# MotorControl.net
KiCad netlist of a schematic drawn in Altium Designer
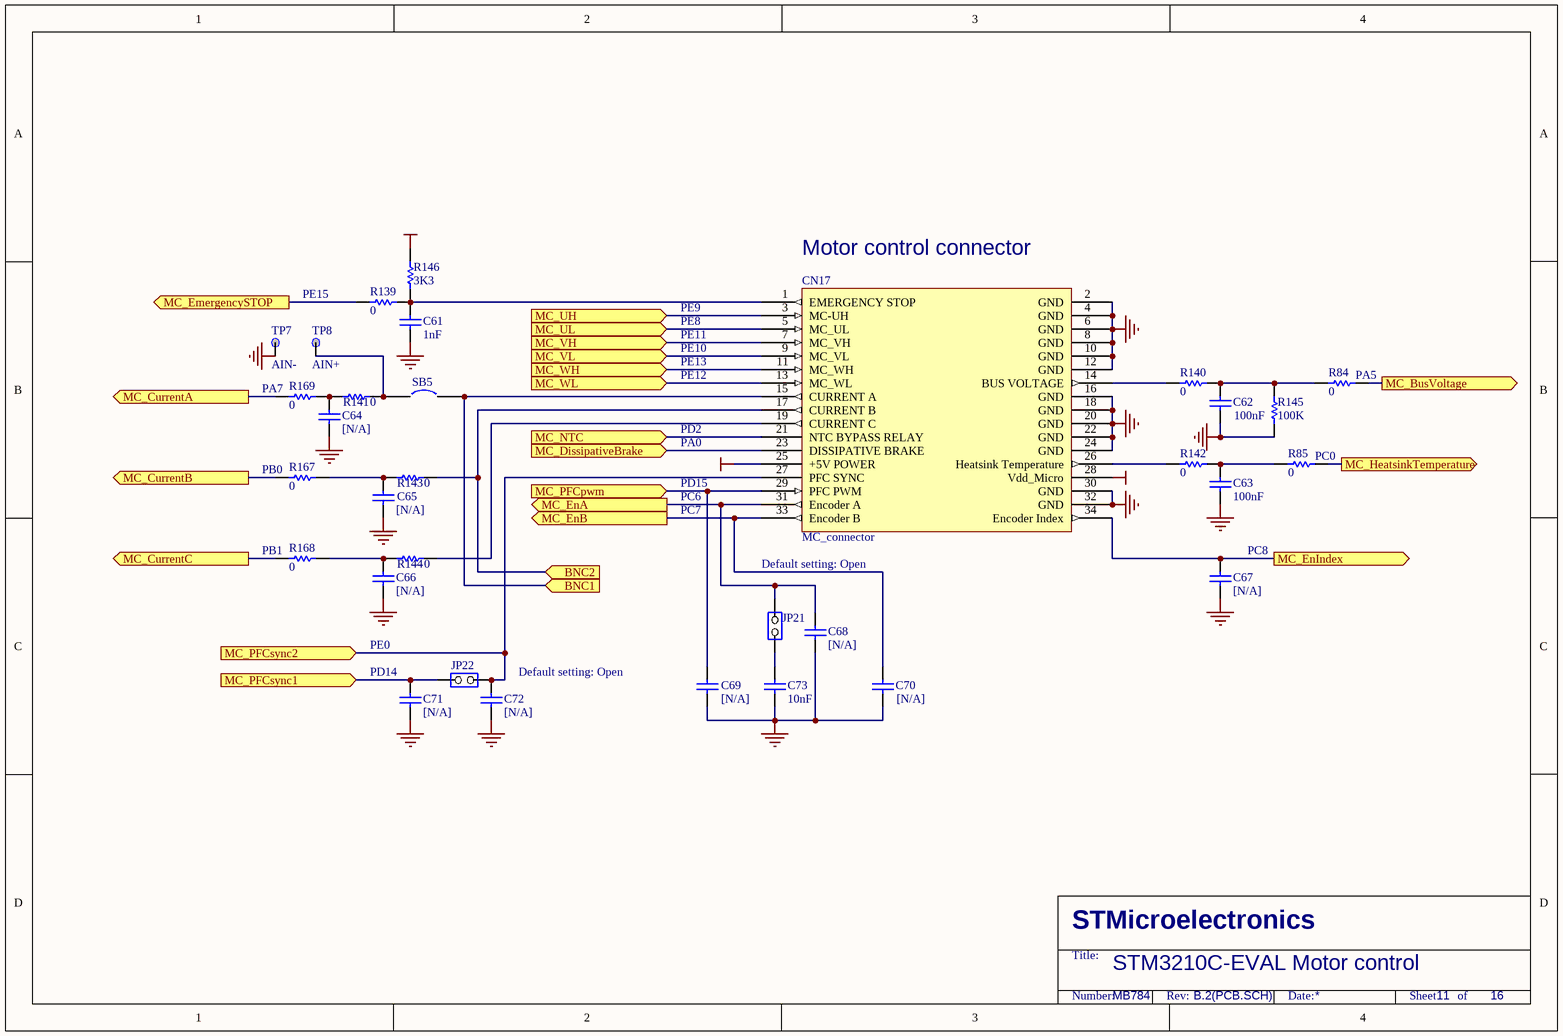
[diagram p0: MotorControl.SchDoc]

(export (version "E")
  (design (tool "Eeschema 10.0.6"))
  (components
    (comp (ref "C61")
      (value "1nF")
      (footprint "0603C")
      (description "Capacitor")
      (fields (field (name "PUBLISHER") "Altium Limited"))
      (libsource (lib "Miscellaneous Devices") (part "CAP"))
    )
    (comp (ref "C62")
      (value "100nF")
      (footprint "0603C")
      (description "Capacitor")
      (fields (field (name "PUBLISHER") "Altium Limited"))
      (libsource (lib "Miscellaneous Devices") (part "cap"))
    )
    (comp (ref "C63")
      (value "100nF")
      (footprint "0603C")
      (description "Capacitor")
      (fields (field (name "PUBLISHER") "Altium Limited"))
      (libsource (lib "Miscellaneous Devices") (part "cap"))
    )
    (comp (ref "C64")
      (value "[N/A]")
      (footprint "0603C")
      (description "Capacitor")
      (fields (field (name "PUBLISHER") "Altium Limited"))
      (libsource (lib "Miscellaneous Devices") (part "cap"))
    )
    (comp (ref "C65")
      (value "[N/A]")
      (footprint "0603C")
      (description "Capacitor")
      (fields (field (name "PUBLISHER") "Altium Limited"))
      (libsource (lib "Miscellaneous Devices") (part "cap"))
    )
    (comp (ref "C66")
      (value "[N/A]")
      (footprint "0603C")
      (description "Capacitor")
      (fields (field (name "PUBLISHER") "Altium Limited"))
      (libsource (lib "Miscellaneous Devices") (part "cap"))
    )
    (comp (ref "C67")
      (value "[N/A]")
      (footprint "0603C")
      (description "Capacitor")
      (fields (field (name "PUBLISHER") "Altium Limited"))
      (libsource (lib "Miscellaneous Devices") (part "cap"))
    )
    (comp (ref "C68")
      (value "[N/A]")
      (footprint "0603C")
      (description "Capacitor")
      (fields (field (name "PUBLISHER") "Altium Limited"))
      (libsource (lib "Miscellaneous Devices") (part "cap"))
    )
    (comp (ref "C69")
      (value "[N/A]")
      (footprint "0603C")
      (description "Capacitor")
      (fields (field (name "PUBLISHER") "Altium Limited"))
      (libsource (lib "Miscellaneous Devices") (part "cap"))
    )
    (comp (ref "C70")
      (value "[N/A]")
      (footprint "0603C")
      (description "Capacitor")
      (fields (field (name "PUBLISHER") "Altium Limited"))
      (libsource (lib "Miscellaneous Devices") (part "cap"))
    )
    (comp (ref "C71")
      (value "[N/A]")
      (footprint "0603C")
      (description "Capacitor")
      (fields (field (name "PUBLISHER") "Altium Limited"))
      (libsource (lib "Miscellaneous Devices") (part "cap"))
    )
    (comp (ref "C72")
      (value "[N/A]")
      (footprint "0603C")
      (description "Capacitor")
      (fields (field (name "PUBLISHER") "Altium Limited"))
      (libsource (lib "Miscellaneous Devices") (part "cap"))
    )
    (comp (ref "C73")
      (value "10nF")
      (footprint "0603C")
      (description "Capacitor")
      (fields (field (name "PUBLISHER") "Altium Limited"))
      (libsource (lib "Miscellaneous Devices") (part "cap"))
    )
    (comp (ref "CN17")
      (value "MC_connector")
      (footprint "IDC34S")
      (libsource (lib "MB525") (part "MC_connector"))
    )
    (comp (ref "JP21") (value "~") (footprint "SIP2") (libsource (lib "*") (part "JP2")))
    (comp (ref "JP22") (value "~") (footprint "SIP2") (libsource (lib "*") (part "JP2")))
    (comp (ref "R84")
      (value "0")
      (footprint "0603R")
      (description "Resistor")
      (fields (field (name "PUBLISHER") "Altium Limited"))
      (libsource (lib "Miscellaneous Devices") (part "Res1"))
    )
    (comp (ref "R85")
      (value "0")
      (footprint "0603R")
      (description "Resistor")
      (fields (field (name "PUBLISHER") "Altium Limited"))
      (libsource (lib "Miscellaneous Devices") (part "Res1"))
    )
    (comp (ref "R139")
      (value "0")
      (footprint "0603R")
      (description "Resistor")
      (fields (field (name "PUBLISHER") "Altium Limited"))
      (libsource (lib "Miscellaneous Devices") (part "Res1"))
    )
    (comp (ref "R140")
      (value "0")
      (footprint "0603R")
      (description "Resistor")
      (fields (field (name "PUBLISHER") "Altium Limited"))
      (libsource (lib "Miscellaneous Devices") (part "Res1"))
    )
    (comp (ref "R141")
      (value "0")
      (footprint "0603R")
      (description "Resistor")
      (fields (field (name "PUBLISHER") "Altium Limited"))
      (libsource (lib "Miscellaneous Devices") (part "Res1"))
    )
    (comp (ref "R142")
      (value "0")
      (footprint "0603R")
      (description "Resistor")
      (fields (field (name "PUBLISHER") "Altium Limited"))
      (libsource (lib "Miscellaneous Devices") (part "Res1"))
    )
    (comp (ref "R143")
      (value "0")
      (footprint "0603R")
      (description "Resistor")
      (fields (field (name "PUBLISHER") "Altium Limited"))
      (libsource (lib "Miscellaneous Devices") (part "Res1"))
    )
    (comp (ref "R144")
      (value "0")
      (footprint "0603R")
      (description "Resistor")
      (fields (field (name "PUBLISHER") "Altium Limited"))
      (libsource (lib "Miscellaneous Devices") (part "Res1"))
    )
    (comp (ref "R145")
      (value "100K")
      (footprint "0603R")
      (description "Resistor")
      (fields (field (name "PUBLISHER") "Altium Limited"))
      (libsource (lib "Miscellaneous Devices") (part "Res1"))
    )
    (comp (ref "R146")
      (value "3K3")
      (footprint "0603R")
      (description "Resistor")
      (fields (field (name "PUBLISHER") "Altium Limited"))
      (libsource (lib "Miscellaneous Devices") (part "Res1"))
    )
    (comp (ref "R167")
      (value "0")
      (footprint "0603R")
      (description "Resistor")
      (fields (field (name "PUBLISHER") "Altium Limited"))
      (libsource (lib "Miscellaneous Devices") (part "Res1"))
    )
    (comp (ref "R168")
      (value "0")
      (footprint "0603R")
      (description "Resistor")
      (fields (field (name "PUBLISHER") "Altium Limited"))
      (libsource (lib "Miscellaneous Devices") (part "Res1"))
    )
    (comp (ref "R169")
      (value "0")
      (footprint "0603R")
      (description "Resistor")
      (fields (field (name "PUBLISHER") "Altium Limited"))
      (libsource (lib "Miscellaneous Devices") (part "Res1"))
    )
    (comp (ref "SB5")
      (value "~")
      (footprint "JP2_SMD")
      (description "Circuit Breaker")
      (fields (field (name "PUBLISHER") "Altium Limited"))
      (libsource (lib "Miscellaneous Devices") (part "Circuit Breaker"))
    )
    (comp (ref "TP7") (value "AIN-") (footprint "TP") (libsource (lib "*") (part "TP")))
    (comp (ref "TP8") (value "AIN+") (footprint "TP") (libsource (lib "*") (part "TP")))
  )
  (nets
    (net (code "1") (name "+3V3") (class "Default")
      (node (ref "CN17") (pin "28") (pinfunction "Vdd_Micro_28") (pintype "power_in"))
      (node (ref "R146") (pin "2") (pinfunction "2_2") (pintype "passive"))
    )
    (net (code "2") (name "+5V") (class "Default")
      (node (ref "CN17") (pin "25") (pinfunction "+5V_POWER_25") (pintype "power_in"))
    )
    (net (code "3") (name "/BNC1") (class "Default")
      (node (ref "CN17") (pin "15") (pinfunction "CURRENT_A_15") (pintype "output"))
      (node (ref "SB5") (pin "2") (pinfunction "2_2") (pintype "passive"))
    )
    (net (code "4") (name "/BNC2") (class "Default")
      (node (ref "CN17") (pin "17") (pinfunction "CURRENT_B_17") (pintype "output"))
      (node (ref "R143") (pin "2") (pinfunction "2_2") (pintype "passive"))
    )
    (net (code "5") (name "/MC_BusVoltage") (class "Default")
      (node (ref "R84") (pin "2") (pinfunction "2_2") (pintype "passive"))
    )
    (net (code "6") (name "/MC_CurrentA") (class "Default")
      (node (ref "R169") (pin "1") (pinfunction "1_1") (pintype "passive"))
    )
    (net (code "7") (name "/MC_CurrentB") (class "Default")
      (node (ref "R167") (pin "1") (pinfunction "1_1") (pintype "passive"))
    )
    (net (code "8") (name "/MC_CurrentC") (class "Default")
      (node (ref "R168") (pin "1") (pinfunction "1_1") (pintype "passive"))
    )
    (net (code "9") (name "/MC_DissipativeBrake") (class "Default")
      (node (ref "CN17") (pin "23") (pinfunction "DISSIPATIVE_BRAKE_23") (pintype "passive"))
    )
    (net (code "10") (name "/MC_EmergencySTOP") (class "Default")
      (node (ref "R139") (pin "2") (pinfunction "2_2") (pintype "passive"))
    )
    (net (code "11") (name "/MC_EnA") (class "Default")
      (node (ref "C68") (pin "2") (pinfunction "2_2") (pintype "passive"))
      (node (ref "CN17") (pin "31") (pinfunction "Encoder_A_31") (pintype "output"))
      (node (ref "JP21") (pin "1") (pinfunction "COMMON_1") (pintype "passive"))
    )
    (net (code "12") (name "/MC_EnB") (class "Default")
      (node (ref "C70") (pin "2") (pinfunction "2_2") (pintype "passive"))
      (node (ref "CN17") (pin "33") (pinfunction "Encoder_B_33") (pintype "output"))
    )
    (net (code "13") (name "/MC_EnIndex") (class "Default")
      (node (ref "C67") (pin "2") (pinfunction "2_2") (pintype "passive"))
      (node (ref "CN17") (pin "34") (pinfunction "Encoder_Index_34") (pintype "output"))
    )
    (net (code "14") (name "/MC_HeatsinkTemperature") (class "Default")
      (node (ref "R85") (pin "2") (pinfunction "2_2") (pintype "passive"))
    )
    (net (code "15") (name "/MC_NTC") (class "Default")
      (node (ref "CN17") (pin "21") (pinfunction "NTC_BYPASS_RELAY_21") (pintype "passive"))
    )
    (net (code "16") (name "/MC_PFCpwm") (class "Default")
      (node (ref "C69") (pin "2") (pinfunction "2_2") (pintype "passive"))
      (node (ref "CN17") (pin "29") (pinfunction "PFC_PWM_29") (pintype "input"))
    )
    (net (code "17") (name "/MC_PFCsync1") (class "Default")
      (node (ref "C71") (pin "2") (pinfunction "2_2") (pintype "passive"))
      (node (ref "JP22") (pin "2") (pinfunction "NO_2") (pintype "passive"))
    )
    (net (code "18") (name "/MC_PFCsync2") (class "Default")
      (node (ref "C72") (pin "2") (pinfunction "2_2") (pintype "passive"))
      (node (ref "CN17") (pin "27") (pinfunction "PFC_SYNC_27") (pintype "passive"))
      (node (ref "JP22") (pin "1") (pinfunction "COMMON_1") (pintype "passive"))
    )
    (net (code "19") (name "/MC_UH") (class "Default")
      (node (ref "CN17") (pin "3") (pinfunction "MC-UH_3") (pintype "input"))
    )
    (net (code "20") (name "/MC_UL") (class "Default")
      (node (ref "CN17") (pin "5") (pinfunction "MC_UL_5") (pintype "input"))
    )
    (net (code "21") (name "/MC_VH") (class "Default")
      (node (ref "CN17") (pin "7") (pinfunction "MC_VH_7") (pintype "input"))
    )
    (net (code "22") (name "/MC_VL") (class "Default")
      (node (ref "CN17") (pin "9") (pinfunction "MC_VL_9") (pintype "input"))
    )
    (net (code "23") (name "/MC_WH") (class "Default")
      (node (ref "CN17") (pin "11") (pinfunction "MC_WH_11") (pintype "input"))
    )
    (net (code "24") (name "/MC_WL") (class "Default")
      (node (ref "CN17") (pin "13") (pinfunction "MC_WL_13") (pintype "input"))
    )
    (net (code "25") (name "GND") (class "Default")
      (node (ref "C61") (pin "1") (pinfunction "1_1") (pintype "passive"))
      (node (ref "C62") (pin "1") (pinfunction "1_1") (pintype "passive"))
      (node (ref "C63") (pin "1") (pinfunction "1_1") (pintype "passive"))
      (node (ref "C64") (pin "1") (pinfunction "1_1") (pintype "passive"))
      (node (ref "C65") (pin "1") (pinfunction "1_1") (pintype "passive"))
      (node (ref "C66") (pin "1") (pinfunction "1_1") (pintype "passive"))
      (node (ref "C67") (pin "1") (pinfunction "1_1") (pintype "passive"))
      (node (ref "C68") (pin "1") (pinfunction "1_1") (pintype "passive"))
      (node (ref "C69") (pin "1") (pinfunction "1_1") (pintype "passive"))
      (node (ref "C70") (pin "1") (pinfunction "1_1") (pintype "passive"))
      (node (ref "C71") (pin "1") (pinfunction "1_1") (pintype "passive"))
      (node (ref "C72") (pin "1") (pinfunction "1_1") (pintype "passive"))
      (node (ref "C73") (pin "1") (pinfunction "1_1") (pintype "passive"))
      (node (ref "CN17") (pin "10") (pinfunction "GND_10") (pintype "power_in"))
      (node (ref "CN17") (pin "12") (pinfunction "GND_12") (pintype "power_in"))
      (node (ref "CN17") (pin "16") (pinfunction "GND_16") (pintype "power_in"))
      (node (ref "CN17") (pin "18") (pinfunction "GND_18") (pintype "power_in"))
      (node (ref "CN17") (pin "2") (pinfunction "GND_2") (pintype "power_in"))
      (node (ref "CN17") (pin "20") (pinfunction "GND_20") (pintype "power_in"))
      (node (ref "CN17") (pin "22") (pinfunction "GND_22") (pintype "power_in"))
      (node (ref "CN17") (pin "24") (pinfunction "GND_24") (pintype "power_in"))
      (node (ref "CN17") (pin "30") (pinfunction "GND_30") (pintype "power_in"))
      (node (ref "CN17") (pin "32") (pinfunction "GND_32") (pintype "power_in"))
      (node (ref "CN17") (pin "4") (pinfunction "GND_4") (pintype "power_in"))
      (node (ref "CN17") (pin "6") (pinfunction "GND_6") (pintype "power_in"))
      (node (ref "CN17") (pin "8") (pinfunction "GND_8") (pintype "power_in"))
      (node (ref "R145") (pin "1") (pinfunction "1_1") (pintype "passive"))
      (node (ref "TP7") (pin "1") (pinfunction "1_1") (pintype "passive"))
    )
    (net (code "26") (name "Net-(C62-Pad2)") (class "Default")
      (node (ref "C62") (pin "2") (pinfunction "2_2") (pintype "passive"))
      (node (ref "R140") (pin "2") (pinfunction "2_2") (pintype "passive"))
      (node (ref "R145") (pin "2") (pinfunction "2_2") (pintype "passive"))
      (node (ref "R84") (pin "1") (pinfunction "1_1") (pintype "passive"))
    )
    (net (code "27") (name "Net-(C63-Pad2)") (class "Default")
      (node (ref "C63") (pin "2") (pinfunction "2_2") (pintype "passive"))
      (node (ref "R142") (pin "2") (pinfunction "2_2") (pintype "passive"))
      (node (ref "R85") (pin "1") (pinfunction "1_1") (pintype "passive"))
    )
    (net (code "28") (name "Net-(C64-Pad2)") (class "Default")
      (node (ref "C64") (pin "2") (pinfunction "2_2") (pintype "passive"))
      (node (ref "R141") (pin "1") (pinfunction "1_1") (pintype "passive"))
      (node (ref "R169") (pin "2") (pinfunction "2_2") (pintype "passive"))
    )
    (net (code "29") (name "Net-(C65-Pad2)") (class "Default")
      (node (ref "C65") (pin "2") (pinfunction "2_2") (pintype "passive"))
      (node (ref "R143") (pin "1") (pinfunction "1_1") (pintype "passive"))
      (node (ref "R167") (pin "2") (pinfunction "2_2") (pintype "passive"))
    )
    (net (code "30") (name "Net-(C66-Pad2)") (class "Default")
      (node (ref "C66") (pin "2") (pinfunction "2_2") (pintype "passive"))
      (node (ref "R144") (pin "1") (pinfunction "1_1") (pintype "passive"))
      (node (ref "R168") (pin "2") (pinfunction "2_2") (pintype "passive"))
    )
    (net (code "31") (name "Net-(CN17-BUS_VOLTAGE)") (class "Default")
      (node (ref "CN17") (pin "14") (pinfunction "BUS_VOLTAGE_14") (pintype "output"))
      (node (ref "R140") (pin "1") (pinfunction "1_1") (pintype "passive"))
    )
    (net (code "32") (name "Net-(CN17-CURRENT_C)") (class "Default")
      (node (ref "CN17") (pin "19") (pinfunction "CURRENT_C_19") (pintype "output"))
      (node (ref "R144") (pin "2") (pinfunction "2_2") (pintype "passive"))
    )
    (net (code "33") (name "Net-(CN17-EMERGENCY_STOP)") (class "Default")
      (node (ref "C61") (pin "2") (pinfunction "2_2") (pintype "passive"))
      (node (ref "CN17") (pin "1") (pinfunction "EMERGENCY_STOP_1") (pintype "output"))
      (node (ref "R139") (pin "1") (pinfunction "1_1") (pintype "passive"))
      (node (ref "R146") (pin "1") (pinfunction "1_1") (pintype "passive"))
    )
    (net (code "34") (name "Net-(CN17-Heatsink_Temperature)") (class "Default")
      (node (ref "CN17") (pin "26") (pinfunction "Heatsink_Temperature_26") (pintype "output"))
      (node (ref "R142") (pin "1") (pinfunction "1_1") (pintype "passive"))
    )
    (net (code "35") (name "Net-(JP21-NO)") (class "Default")
      (node (ref "C73") (pin "2") (pinfunction "2_2") (pintype "passive"))
      (node (ref "JP21") (pin "2") (pinfunction "NO_2") (pintype "passive"))
    )
    (net (code "36") (name "Net-(R141-Pad2)") (class "Default")
      (node (ref "R141") (pin "2") (pinfunction "2_2") (pintype "passive"))
      (node (ref "SB5") (pin "1") (pinfunction "1_1") (pintype "passive"))
      (node (ref "TP8") (pin "1") (pinfunction "1_1") (pintype "passive"))
    )
  )
)
